# NL_Sheet1.net
KiCad netlist of a schematic drawn in Altium Designer
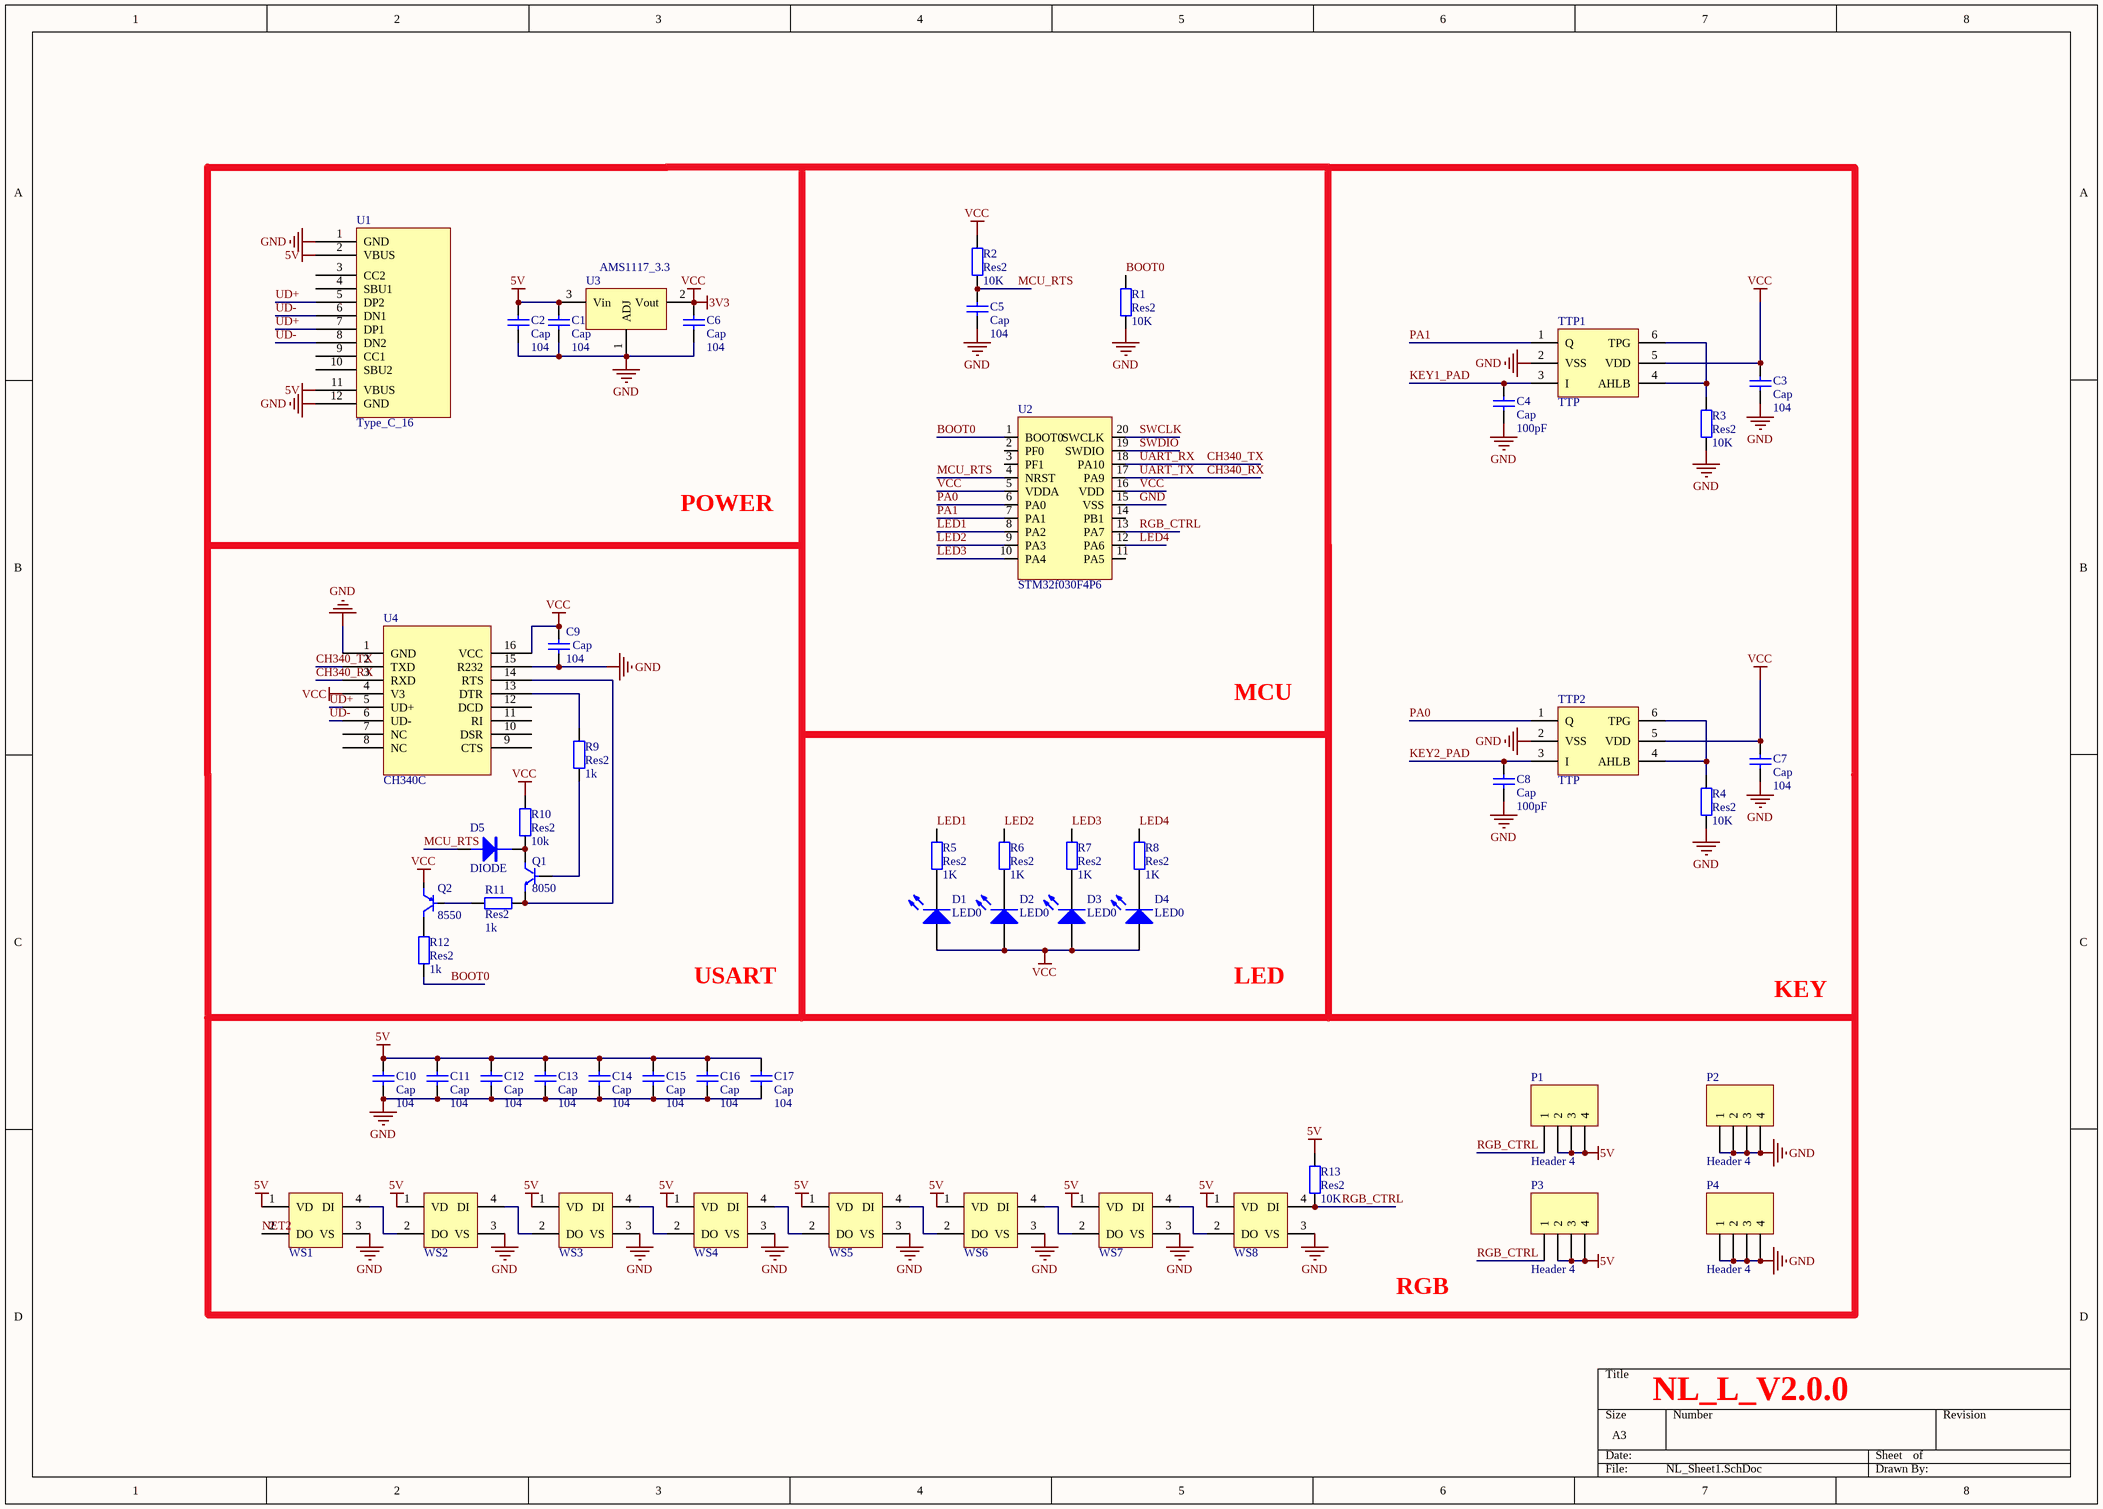
[diagram p0: NL_Sheet1.SchDoc]

(export (version "E")
  (design (tool "Eeschema 10.0.6"))
  (components
    (comp (ref "C1")
      (value "Cap")
      (footprint "0805")
      (description "Capacitor")
      (fields (field (name "ALTIUM_VALUE") "104") (field (name "PUBLISHER") "Altium Limited"))
      (libsource (lib "Miscellaneous Devices") (part "Cap"))
    )
    (comp (ref "C2")
      (value "Cap")
      (footprint "0805")
      (description "Capacitor")
      (fields (field (name "ALTIUM_VALUE") "104") (field (name "PUBLISHER") "Altium Limited"))
      (libsource (lib "Miscellaneous Devices") (part "Cap"))
    )
    (comp (ref "C3")
      (value "Cap")
      (footprint "0805")
      (description "Capacitor")
      (fields (field (name "ALTIUM_VALUE") "104") (field (name "PUBLISHER") "Altium Limited"))
      (libsource (lib "Miscellaneous Devices") (part "Cap"))
    )
    (comp (ref "C4")
      (value "Cap")
      (footprint "0805")
      (description "Capacitor")
      (fields (field (name "ALTIUM_VALUE") "100pF") (field (name "PUBLISHER") "Altium Limited"))
      (libsource (lib "Miscellaneous Devices") (part "Cap"))
    )
    (comp (ref "C5")
      (value "Cap")
      (footprint "0805")
      (description "Capacitor")
      (fields (field (name "ALTIUM_VALUE") "104") (field (name "PUBLISHER") "Altium Limited"))
      (libsource (lib "Miscellaneous Devices") (part "Cap"))
    )
    (comp (ref "C6")
      (value "Cap")
      (footprint "0805")
      (description "Capacitor")
      (fields (field (name "ALTIUM_VALUE") "104") (field (name "PUBLISHER") "Altium Limited"))
      (libsource (lib "Miscellaneous Devices") (part "Cap"))
    )
    (comp (ref "C7")
      (value "Cap")
      (footprint "0805")
      (description "Capacitor")
      (fields (field (name "ALTIUM_VALUE") "104") (field (name "PUBLISHER") "Altium Limited"))
      (libsource (lib "Miscellaneous Devices") (part "Cap"))
    )
    (comp (ref "C8")
      (value "Cap")
      (footprint "0805")
      (description "Capacitor")
      (fields (field (name "ALTIUM_VALUE") "100pF") (field (name "PUBLISHER") "Altium Limited"))
      (libsource (lib "Miscellaneous Devices") (part "Cap"))
    )
    (comp (ref "C9")
      (value "Cap")
      (footprint "0805")
      (description "Capacitor")
      (fields (field (name "ALTIUM_VALUE") "104") (field (name "PUBLISHER") "Altium Limited"))
      (libsource (lib "Miscellaneous Devices") (part "Cap"))
    )
    (comp (ref "C10")
      (value "Cap")
      (footprint "0805")
      (description "Capacitor")
      (fields (field (name "ALTIUM_VALUE") "104") (field (name "PUBLISHER") "Altium Limited"))
      (libsource (lib "NL_PCB_Project") (part "Cap"))
    )
    (comp (ref "C11")
      (value "Cap")
      (footprint "0805")
      (description "Capacitor")
      (fields (field (name "ALTIUM_VALUE") "104") (field (name "PUBLISHER") "Altium Limited"))
      (libsource (lib "NL_PCB_Project") (part "Cap"))
    )
    (comp (ref "C12")
      (value "Cap")
      (footprint "0805")
      (description "Capacitor")
      (fields (field (name "ALTIUM_VALUE") "104") (field (name "PUBLISHER") "Altium Limited"))
      (libsource (lib "NL_PCB_Project") (part "Cap"))
    )
    (comp (ref "C13")
      (value "Cap")
      (footprint "0805")
      (description "Capacitor")
      (fields (field (name "ALTIUM_VALUE") "104") (field (name "PUBLISHER") "Altium Limited"))
      (libsource (lib "NL_PCB_Project") (part "Cap"))
    )
    (comp (ref "C14")
      (value "Cap")
      (footprint "0805")
      (description "Capacitor")
      (fields (field (name "ALTIUM_VALUE") "104") (field (name "PUBLISHER") "Altium Limited"))
      (libsource (lib "NL_PCB_Project") (part "Cap"))
    )
    (comp (ref "C15")
      (value "Cap")
      (footprint "0805")
      (description "Capacitor")
      (fields (field (name "ALTIUM_VALUE") "104") (field (name "PUBLISHER") "Altium Limited"))
      (libsource (lib "NL_PCB_Project") (part "Cap"))
    )
    (comp (ref "C16")
      (value "Cap")
      (footprint "0805")
      (description "Capacitor")
      (fields (field (name "ALTIUM_VALUE") "104") (field (name "PUBLISHER") "Altium Limited"))
      (libsource (lib "NL_PCB_Project") (part "Cap"))
    )
    (comp (ref "C17")
      (value "Cap")
      (footprint "0805")
      (description "Capacitor")
      (fields (field (name "ALTIUM_VALUE") "104") (field (name "PUBLISHER") "Altium Limited"))
      (libsource (lib "NL_PCB_Project") (part "Cap"))
    )
    (comp (ref "D1")
      (value "LED0")
      (footprint "0805")
      (description "Typical INFRARED GaAs LED")
      (fields (field (name "PUBLISHER") "Altium Limited"))
      (libsource (lib "Miscellaneous Devices") (part "LED0"))
    )
    (comp (ref "D2")
      (value "LED0")
      (footprint "0805")
      (description "Typical INFRARED GaAs LED")
      (fields (field (name "PUBLISHER") "Altium Limited"))
      (libsource (lib "Miscellaneous Devices") (part "LED0"))
    )
    (comp (ref "D3")
      (value "LED0")
      (footprint "0805")
      (description "Typical INFRARED GaAs LED")
      (fields (field (name "PUBLISHER") "Altium Limited"))
      (libsource (lib "Miscellaneous Devices") (part "LED0"))
    )
    (comp (ref "D4")
      (value "LED0")
      (footprint "0805")
      (description "Typical INFRARED GaAs LED")
      (fields (field (name "PUBLISHER") "Altium Limited"))
      (libsource (lib "Miscellaneous Devices") (part "LED0"))
    )
    (comp (ref "D5") (value "DIODE") (footprint "0805L") (libsource (lib "常用1") (part "DIODE")))
    (comp (ref "P1")
      (value "Header 4")
      (footprint "HDR1X4")
      (description "Header, 4-Pin")
      (fields (field (name "PUBLISHER") "Altium Limited"))
      (libsource (lib "Miscellaneous Connectors") (part "Header 4"))
    )
    (comp (ref "P2")
      (value "Header 4")
      (footprint "HDR1X4")
      (description "Header, 4-Pin")
      (fields (field (name "PUBLISHER") "Altium Limited"))
      (libsource (lib "Miscellaneous Connectors") (part "Header 4"))
    )
    (comp (ref "P3")
      (value "Header 4")
      (footprint "HDR1X4")
      (description "Header, 4-Pin")
      (fields (field (name "PUBLISHER") "Altium Limited"))
      (libsource (lib "Miscellaneous Connectors") (part "Header 4"))
    )
    (comp (ref "P4")
      (value "Header 4")
      (footprint "HDR1X4")
      (description "Header, 4-Pin")
      (fields (field (name "PUBLISHER") "Altium Limited"))
      (libsource (lib "Miscellaneous Connectors") (part "Header 4"))
    )
    (comp (ref "Q1") (value "8050") (footprint "SOT23") (libsource (lib "NL_PCB_Project") (part "NPN")))
    (comp (ref "Q2") (value "8550") (footprint "SOT23") (libsource (lib "NL_PCB_Project") (part "PNP")))
    (comp (ref "R1")
      (value "Res2")
      (footprint "0805")
      (description "Resistor")
      (fields (field (name "ALTIUM_VALUE") "10K") (field (name "PUBLISHER") "Altium Limited"))
      (libsource (lib "Miscellaneous Devices") (part "Res2"))
    )
    (comp (ref "R2")
      (value "Res2")
      (footprint "0805")
      (description "Resistor")
      (fields (field (name "ALTIUM_VALUE") "10K") (field (name "PUBLISHER") "Altium Limited"))
      (libsource (lib "Miscellaneous Devices") (part "Res2"))
    )
    (comp (ref "R3")
      (value "Res2")
      (footprint "0805")
      (description "Resistor")
      (fields (field (name "ALTIUM_VALUE") "10K") (field (name "PUBLISHER") "Altium Limited"))
      (libsource (lib "Miscellaneous Devices") (part "Res2"))
    )
    (comp (ref "R4")
      (value "Res2")
      (footprint "0805")
      (description "Resistor")
      (fields (field (name "ALTIUM_VALUE") "10K") (field (name "PUBLISHER") "Altium Limited"))
      (libsource (lib "Miscellaneous Devices") (part "Res2"))
    )
    (comp (ref "R5")
      (value "Res2")
      (footprint "0805")
      (description "Resistor")
      (fields (field (name "ALTIUM_VALUE") "1K") (field (name "PUBLISHER") "Altium Limited"))
      (libsource (lib "Miscellaneous Devices") (part "Res2"))
    )
    (comp (ref "R6")
      (value "Res2")
      (footprint "0805")
      (description "Resistor")
      (fields (field (name "ALTIUM_VALUE") "1K") (field (name "PUBLISHER") "Altium Limited"))
      (libsource (lib "Miscellaneous Devices") (part "Res2"))
    )
    (comp (ref "R7")
      (value "Res2")
      (footprint "0805")
      (description "Resistor")
      (fields (field (name "ALTIUM_VALUE") "1K") (field (name "PUBLISHER") "Altium Limited"))
      (libsource (lib "Miscellaneous Devices") (part "Res2"))
    )
    (comp (ref "R8")
      (value "Res2")
      (footprint "0805")
      (description "Resistor")
      (fields (field (name "ALTIUM_VALUE") "1K") (field (name "PUBLISHER") "Altium Limited"))
      (libsource (lib "Miscellaneous Devices") (part "Res2"))
    )
    (comp (ref "R9")
      (value "Res2")
      (footprint "0805")
      (description "Resistor")
      (fields (field (name "ALTIUM_VALUE") "1k") (field (name "PUBLISHER") "Altium Limited"))
      (libsource (lib "") (part "Res2_1"))
    )
    (comp (ref "R10")
      (value "Res2")
      (footprint "0805")
      (description "Resistor")
      (fields (field (name "ALTIUM_VALUE") "10k") (field (name "PUBLISHER") "Altium Limited"))
      (libsource (lib "") (part "Res2_1"))
    )
    (comp (ref "R11")
      (value "Res2")
      (footprint "0805")
      (description "Resistor")
      (fields (field (name "ALTIUM_VALUE") "1k") (field (name "PUBLISHER") "Altium Limited"))
      (libsource (lib "") (part "Res2_2"))
    )
    (comp (ref "R12")
      (value "Res2")
      (footprint "0805")
      (description "Resistor")
      (fields (field (name "ALTIUM_VALUE") "1k") (field (name "PUBLISHER") "Altium Limited"))
      (libsource (lib "Miscellaneous Devices") (part "Res2"))
    )
    (comp (ref "R13")
      (value "Res2")
      (footprint "0805")
      (description "Resistor")
      (fields (field (name "ALTIUM_VALUE") "10K") (field (name "PUBLISHER") "Altium Limited"))
      (libsource (lib "Miscellaneous Devices") (part "Res2"))
    )
    (comp (ref "TTP1") (value "TTP") (footprint "SOT23-6L") (libsource (lib "常用1") (part "TTP223")))
    (comp (ref "TTP2") (value "TTP") (footprint "SOT23-6L") (libsource (lib "常用1") (part "TTP223")))
    (comp (ref "U1") (value "Type_C_16") (footprint "Type_C16") (libsource (lib "常用1") (part "Type_C_16")))
    (comp (ref "U2")
      (value "STM32f030F4P6")
      (footprint "SSOP20")
      (libsource (lib "ST Microcontrol") (part "STM32f030F4P6"))
    )
    (comp (ref "U3")
      (value "AMS1117_3.3")
      (footprint "SOT-223")
      (description "3-Terminal Adjustable Positive Voltage Regulator")
      (libsource (lib "稳压器件") (part "LM317"))
    )
    (comp (ref "U4") (value "CH340C") (footprint "SOP16") (libsource (lib "常用1") (part "CH340C")))
    (comp (ref "WS1") (value "WS2812") (footprint "WS2812") (libsource (lib "常用1") (part "WS2812")))
    (comp (ref "WS2") (value "WS2812") (footprint "WS2812") (libsource (lib "常用1") (part "WS2812")))
    (comp (ref "WS3") (value "WS2812") (footprint "WS2812") (libsource (lib "常用1") (part "WS2812")))
    (comp (ref "WS4") (value "WS2812") (footprint "WS2812") (libsource (lib "常用1") (part "WS2812")))
    (comp (ref "WS5") (value "WS2812") (footprint "WS2812") (libsource (lib "常用1") (part "WS2812")))
    (comp (ref "WS6") (value "WS2812") (footprint "WS2812") (libsource (lib "常用1") (part "WS2812")))
    (comp (ref "WS7") (value "WS2812") (footprint "WS2812") (libsource (lib "常用1") (part "WS2812")))
    (comp (ref "WS8") (value "WS2812") (footprint "WS2812") (libsource (lib "常用1") (part "WS2812")))
  )
  (nets
    (net (code "1") (name "/BOOT0") (class "Default")
      (node (ref "R1") (pin "2") (pinfunction "2_2") (pintype "passive"))
      (node (ref "R12") (pin "1") (pinfunction "1_1") (pintype "passive"))
      (node (ref "U2") (pin "1") (pinfunction "BOOT0_1") (pintype "passive"))
    )
    (net (code "2") (name "/CH340_RX") (class "Default")
      (node (ref "U2") (pin "17") (pinfunction "PA9_17") (pintype "passive"))
      (node (ref "U4") (pin "3") (pinfunction "RXD_3") (pintype "passive"))
    )
    (net (code "3") (name "/CH340_TX") (class "Default")
      (node (ref "U2") (pin "18") (pinfunction "PA10_18") (pintype "passive"))
      (node (ref "U4") (pin "2") (pinfunction "TXD_2") (pintype "passive"))
    )
    (net (code "4") (name "/KEY1_PAD") (class "Default")
      (node (ref "C4") (pin "2") (pinfunction "2_2") (pintype "passive"))
      (node (ref "TTP1") (pin "3") (pinfunction "I_3") (pintype "passive"))
    )
    (net (code "5") (name "/KEY2_PAD") (class "Default")
      (node (ref "C8") (pin "2") (pinfunction "2_2") (pintype "passive"))
      (node (ref "TTP2") (pin "3") (pinfunction "I_3") (pintype "passive"))
    )
    (net (code "6") (name "/LED1") (class "Default")
      (node (ref "R5") (pin "2") (pinfunction "2_2") (pintype "passive"))
      (node (ref "U2") (pin "8") (pinfunction "PA2_8") (pintype "passive"))
    )
    (net (code "7") (name "/LED2") (class "Default")
      (node (ref "R6") (pin "2") (pinfunction "2_2") (pintype "passive"))
      (node (ref "U2") (pin "9") (pinfunction "PA3_9") (pintype "passive"))
    )
    (net (code "8") (name "/LED3") (class "Default")
      (node (ref "R7") (pin "2") (pinfunction "2_2") (pintype "passive"))
      (node (ref "U2") (pin "10") (pinfunction "PA4_10") (pintype "passive"))
    )
    (net (code "9") (name "/LED4") (class "Default")
      (node (ref "R8") (pin "2") (pinfunction "2_2") (pintype "passive"))
      (node (ref "U2") (pin "12") (pinfunction "PA6_12") (pintype "passive"))
    )
    (net (code "10") (name "/MCU_RTS") (class "Default")
      (node (ref "C5") (pin "2") (pinfunction "2_2") (pintype "passive"))
      (node (ref "D5") (pin "1") (pintype "passive"))
      (node (ref "R2") (pin "1") (pinfunction "1_1") (pintype "passive"))
      (node (ref "U2") (pin "4") (pinfunction "NRST_4") (pintype "passive"))
    )
    (net (code "11") (name "/NET2") (class "Default")
      (node (ref "WS1") (pin "2") (pinfunction "DO_2") (pintype "passive"))
    )
    (net (code "12") (name "/PA0") (class "Default")
      (node (ref "TTP2") (pin "1") (pinfunction "Q_1") (pintype "passive"))
      (node (ref "U2") (pin "6") (pinfunction "PA0_6") (pintype "passive"))
    )
    (net (code "13") (name "/PA1") (class "Default")
      (node (ref "TTP1") (pin "1") (pinfunction "Q_1") (pintype "passive"))
      (node (ref "U2") (pin "7") (pinfunction "PA1_7") (pintype "passive"))
    )
    (net (code "14") (name "/RGB_CTRL") (class "Default")
      (node (ref "P1") (pin "1") (pinfunction "1_1") (pintype "passive"))
      (node (ref "P3") (pin "1") (pinfunction "1_1") (pintype "passive"))
      (node (ref "R13") (pin "1") (pinfunction "1_1") (pintype "passive"))
      (node (ref "U2") (pin "13") (pinfunction "PA7_13") (pintype "passive"))
      (node (ref "WS8") (pin "4") (pinfunction "DI_4") (pintype "passive"))
    )
    (net (code "15") (name "/SWCLK") (class "Default")
      (node (ref "U2") (pin "20") (pinfunction "SWCLK_20") (pintype "passive"))
    )
    (net (code "16") (name "/SWDIO") (class "Default")
      (node (ref "U2") (pin "19") (pinfunction "SWDIO_19") (pintype "passive"))
    )
    (net (code "17") (name "/UD+") (class "Default")
      (node (ref "U1") (pin "5") (pinfunction "DP2_5") (pintype "passive"))
      (node (ref "U1") (pin "7") (pinfunction "DP1_7") (pintype "passive"))
      (node (ref "U4") (pin "5") (pinfunction "UD+_5") (pintype "passive"))
    )
    (net (code "18") (name "/UD-") (class "Default")
      (node (ref "U1") (pin "6") (pinfunction "DN1_6") (pintype "passive"))
      (node (ref "U1") (pin "8") (pinfunction "DN2_8") (pintype "passive"))
      (node (ref "U4") (pin "6") (pinfunction "UD-_6") (pintype "passive"))
    )
    (net (code "19") (name "3V3") (class "Default")
      (node (ref "C3") (pin "2") (pinfunction "2_2") (pintype "passive"))
      (node (ref "C6") (pin "2") (pinfunction "2_2") (pintype "passive"))
      (node (ref "C7") (pin "2") (pinfunction "2_2") (pintype "passive"))
      (node (ref "C9") (pin "2") (pinfunction "2_2") (pintype "passive"))
      (node (ref "D1") (pin "1") (pinfunction "A_1") (pintype "passive"))
      (node (ref "D2") (pin "1") (pinfunction "A_1") (pintype "passive"))
      (node (ref "D3") (pin "1") (pinfunction "A_1") (pintype "passive"))
      (node (ref "D4") (pin "1") (pinfunction "A_1") (pintype "passive"))
      (node (ref "Q2") (pin "e") (pinfunction "e_e") (pintype "passive"))
      (node (ref "R10") (pin "1") (pinfunction "1_1") (pintype "passive"))
      (node (ref "R2") (pin "2") (pinfunction "2_2") (pintype "passive"))
      (node (ref "TTP1") (pin "5") (pinfunction "VDD_5") (pintype "passive"))
      (node (ref "TTP2") (pin "5") (pinfunction "VDD_5") (pintype "passive"))
      (node (ref "U2") (pin "16") (pinfunction "VDD_16") (pintype "passive"))
      (node (ref "U2") (pin "5") (pinfunction "VDDA_5") (pintype "passive"))
      (node (ref "U3") (pin "2") (pinfunction "Vout_2") (pintype "passive"))
      (node (ref "U4") (pin "16") (pinfunction "VCC_16") (pintype "passive"))
      (node (ref "U4") (pin "4") (pinfunction "V3_4") (pintype "passive"))
    )
    (net (code "20") (name "5V") (class "Default")
      (node (ref "C1") (pin "2") (pinfunction "2_2") (pintype "passive"))
      (node (ref "C10") (pin "2") (pinfunction "2_2") (pintype "passive"))
      (node (ref "C11") (pin "2") (pinfunction "2_2") (pintype "passive"))
      (node (ref "C12") (pin "2") (pinfunction "2_2") (pintype "passive"))
      (node (ref "C13") (pin "2") (pinfunction "2_2") (pintype "passive"))
      (node (ref "C14") (pin "2") (pinfunction "2_2") (pintype "passive"))
      (node (ref "C15") (pin "2") (pinfunction "2_2") (pintype "passive"))
      (node (ref "C16") (pin "2") (pinfunction "2_2") (pintype "passive"))
      (node (ref "C17") (pin "2") (pinfunction "2_2") (pintype "passive"))
      (node (ref "C2") (pin "2") (pinfunction "2_2") (pintype "passive"))
      (node (ref "P1") (pin "2") (pinfunction "2_2") (pintype "passive"))
      (node (ref "P1") (pin "3") (pinfunction "3_3") (pintype "passive"))
      (node (ref "P1") (pin "4") (pinfunction "4_4") (pintype "passive"))
      (node (ref "P3") (pin "2") (pinfunction "2_2") (pintype "passive"))
      (node (ref "P3") (pin "3") (pinfunction "3_3") (pintype "passive"))
      (node (ref "P3") (pin "4") (pinfunction "4_4") (pintype "passive"))
      (node (ref "R13") (pin "2") (pinfunction "2_2") (pintype "passive"))
      (node (ref "U1") (pin "11") (pinfunction "VBUS_11") (pintype "passive"))
      (node (ref "U1") (pin "2") (pinfunction "VBUS_2") (pintype "passive"))
      (node (ref "U3") (pin "3") (pinfunction "Vin_3") (pintype "passive"))
      (node (ref "WS1") (pin "1") (pinfunction "VD_1") (pintype "passive"))
      (node (ref "WS2") (pin "1") (pinfunction "VD_1") (pintype "passive"))
      (node (ref "WS3") (pin "1") (pinfunction "VD_1") (pintype "passive"))
      (node (ref "WS4") (pin "1") (pinfunction "VD_1") (pintype "passive"))
      (node (ref "WS5") (pin "1") (pinfunction "VD_1") (pintype "passive"))
      (node (ref "WS6") (pin "1") (pinfunction "VD_1") (pintype "passive"))
      (node (ref "WS7") (pin "1") (pinfunction "VD_1") (pintype "passive"))
      (node (ref "WS8") (pin "1") (pinfunction "VD_1") (pintype "passive"))
    )
    (net (code "21") (name "GND") (class "Default")
      (node (ref "C1") (pin "1") (pinfunction "1_1") (pintype "passive"))
      (node (ref "C10") (pin "1") (pinfunction "1_1") (pintype "passive"))
      (node (ref "C11") (pin "1") (pinfunction "1_1") (pintype "passive"))
      (node (ref "C12") (pin "1") (pinfunction "1_1") (pintype "passive"))
      (node (ref "C13") (pin "1") (pinfunction "1_1") (pintype "passive"))
      (node (ref "C14") (pin "1") (pinfunction "1_1") (pintype "passive"))
      (node (ref "C15") (pin "1") (pinfunction "1_1") (pintype "passive"))
      (node (ref "C16") (pin "1") (pinfunction "1_1") (pintype "passive"))
      (node (ref "C17") (pin "1") (pinfunction "1_1") (pintype "passive"))
      (node (ref "C2") (pin "1") (pinfunction "1_1") (pintype "passive"))
      (node (ref "C3") (pin "1") (pinfunction "1_1") (pintype "passive"))
      (node (ref "C4") (pin "1") (pinfunction "1_1") (pintype "passive"))
      (node (ref "C5") (pin "1") (pinfunction "1_1") (pintype "passive"))
      (node (ref "C6") (pin "1") (pinfunction "1_1") (pintype "passive"))
      (node (ref "C7") (pin "1") (pinfunction "1_1") (pintype "passive"))
      (node (ref "C8") (pin "1") (pinfunction "1_1") (pintype "passive"))
      (node (ref "C9") (pin "1") (pinfunction "1_1") (pintype "passive"))
      (node (ref "P2") (pin "1") (pinfunction "1_1") (pintype "passive"))
      (node (ref "P2") (pin "2") (pinfunction "2_2") (pintype "passive"))
      (node (ref "P2") (pin "3") (pinfunction "3_3") (pintype "passive"))
      (node (ref "P2") (pin "4") (pinfunction "4_4") (pintype "passive"))
      (node (ref "P4") (pin "1") (pinfunction "1_1") (pintype "passive"))
      (node (ref "P4") (pin "2") (pinfunction "2_2") (pintype "passive"))
      (node (ref "P4") (pin "3") (pinfunction "3_3") (pintype "passive"))
      (node (ref "P4") (pin "4") (pinfunction "4_4") (pintype "passive"))
      (node (ref "R1") (pin "1") (pinfunction "1_1") (pintype "passive"))
      (node (ref "R3") (pin "1") (pinfunction "1_1") (pintype "passive"))
      (node (ref "R4") (pin "1") (pinfunction "1_1") (pintype "passive"))
      (node (ref "TTP1") (pin "2") (pinfunction "VSS_2") (pintype "passive"))
      (node (ref "TTP2") (pin "2") (pinfunction "VSS_2") (pintype "passive"))
      (node (ref "U1") (pin "1") (pinfunction "GND_1") (pintype "passive"))
      (node (ref "U1") (pin "12") (pinfunction "GND_12") (pintype "passive"))
      (node (ref "U2") (pin "15") (pinfunction "VSS_15") (pintype "passive"))
      (node (ref "U3") (pin "1") (pinfunction "ADJ_1") (pintype "passive"))
      (node (ref "U4") (pin "1") (pinfunction "GND_1") (pintype "passive"))
      (node (ref "U4") (pin "15") (pinfunction "R232_15") (pintype "passive"))
      (node (ref "WS1") (pin "3") (pinfunction "VS_3") (pintype "passive"))
      (node (ref "WS2") (pin "3") (pinfunction "VS_3") (pintype "passive"))
      (node (ref "WS3") (pin "3") (pinfunction "VS_3") (pintype "passive"))
      (node (ref "WS4") (pin "3") (pinfunction "VS_3") (pintype "passive"))
      (node (ref "WS5") (pin "3") (pinfunction "VS_3") (pintype "passive"))
      (node (ref "WS6") (pin "3") (pinfunction "VS_3") (pintype "passive"))
      (node (ref "WS7") (pin "3") (pinfunction "VS_3") (pintype "passive"))
      (node (ref "WS8") (pin "3") (pinfunction "VS_3") (pintype "passive"))
    )
    (net (code "22") (name "Net-(D1-K)") (class "Default")
      (node (ref "D1") (pin "2") (pinfunction "K_2") (pintype "passive"))
      (node (ref "R5") (pin "1") (pinfunction "1_1") (pintype "passive"))
    )
    (net (code "23") (name "Net-(D2-K)") (class "Default")
      (node (ref "D2") (pin "2") (pinfunction "K_2") (pintype "passive"))
      (node (ref "R6") (pin "1") (pinfunction "1_1") (pintype "passive"))
    )
    (net (code "24") (name "Net-(D3-K)") (class "Default")
      (node (ref "D3") (pin "2") (pinfunction "K_2") (pintype "passive"))
      (node (ref "R7") (pin "1") (pinfunction "1_1") (pintype "passive"))
    )
    (net (code "25") (name "Net-(D4-K)") (class "Default")
      (node (ref "D4") (pin "2") (pinfunction "K_2") (pintype "passive"))
      (node (ref "R8") (pin "1") (pinfunction "1_1") (pintype "passive"))
    )
    (net (code "26") (name "Net-(D5-Pad2)") (class "Default")
      (node (ref "D5") (pin "2") (pintype "passive"))
      (node (ref "Q1") (pin "c") (pinfunction "c_c") (pintype "passive"))
      (node (ref "R10") (pin "2") (pinfunction "2_2") (pintype "passive"))
    )
    (net (code "27") (name "Net-(Q1-Padb)") (class "Default")
      (node (ref "Q1") (pin "b") (pinfunction "b_b") (pintype "passive"))
      (node (ref "R9") (pin "2") (pinfunction "2_2") (pintype "passive"))
    )
    (net (code "28") (name "Net-(Q2-Padb)") (class "Default")
      (node (ref "Q2") (pin "b") (pinfunction "b_b") (pintype "passive"))
      (node (ref "R11") (pin "1") (pinfunction "1_1") (pintype "passive"))
    )
    (net (code "29") (name "Net-(Q2-Padc)") (class "Default")
      (node (ref "Q2") (pin "c") (pinfunction "c_c") (pintype "passive"))
      (node (ref "R12") (pin "2") (pinfunction "2_2") (pintype "passive"))
    )
    (net (code "30") (name "Net-(TTP1-AHLB)") (class "Default")
      (node (ref "R3") (pin "2") (pinfunction "2_2") (pintype "passive"))
      (node (ref "TTP1") (pin "4") (pinfunction "AHLB_4") (pintype "passive"))
      (node (ref "TTP1") (pin "6") (pinfunction "TPG_6") (pintype "passive"))
    )
    (net (code "31") (name "Net-(TTP2-AHLB)") (class "Default")
      (node (ref "R4") (pin "2") (pinfunction "2_2") (pintype "passive"))
      (node (ref "TTP2") (pin "4") (pinfunction "AHLB_4") (pintype "passive"))
      (node (ref "TTP2") (pin "6") (pinfunction "TPG_6") (pintype "passive"))
    )
    (net (code "32") (name "Net-(U4-DTR)") (class "Default")
      (node (ref "R9") (pin "1") (pinfunction "1_1") (pintype "passive"))
      (node (ref "U4") (pin "13") (pinfunction "DTR_13") (pintype "passive"))
    )
    (net (code "33") (name "Net-(U4-RTS)") (class "Default")
      (node (ref "Q1") (pin "e") (pinfunction "e_e") (pintype "passive"))
      (node (ref "R11") (pin "2") (pinfunction "2_2") (pintype "passive"))
      (node (ref "U4") (pin "14") (pinfunction "RTS_14") (pintype "passive"))
    )
    (net (code "34") (name "Net-(WS1-DI)") (class "Default")
      (node (ref "WS1") (pin "4") (pinfunction "DI_4") (pintype "passive"))
      (node (ref "WS2") (pin "2") (pinfunction "DO_2") (pintype "passive"))
    )
    (net (code "35") (name "Net-(WS2-DI)") (class "Default")
      (node (ref "WS2") (pin "4") (pinfunction "DI_4") (pintype "passive"))
      (node (ref "WS3") (pin "2") (pinfunction "DO_2") (pintype "passive"))
    )
    (net (code "36") (name "Net-(WS3-DI)") (class "Default")
      (node (ref "WS3") (pin "4") (pinfunction "DI_4") (pintype "passive"))
      (node (ref "WS4") (pin "2") (pinfunction "DO_2") (pintype "passive"))
    )
    (net (code "37") (name "Net-(WS4-DI)") (class "Default")
      (node (ref "WS4") (pin "4") (pinfunction "DI_4") (pintype "passive"))
      (node (ref "WS5") (pin "2") (pinfunction "DO_2") (pintype "passive"))
    )
    (net (code "38") (name "Net-(WS5-DI)") (class "Default")
      (node (ref "WS5") (pin "4") (pinfunction "DI_4") (pintype "passive"))
      (node (ref "WS6") (pin "2") (pinfunction "DO_2") (pintype "passive"))
    )
    (net (code "39") (name "Net-(WS6-DI)") (class "Default")
      (node (ref "WS6") (pin "4") (pinfunction "DI_4") (pintype "passive"))
      (node (ref "WS7") (pin "2") (pinfunction "DO_2") (pintype "passive"))
    )
    (net (code "40") (name "Net-(WS7-DI)") (class "Default")
      (node (ref "WS7") (pin "4") (pinfunction "DI_4") (pintype "passive"))
      (node (ref "WS8") (pin "2") (pinfunction "DO_2") (pintype "passive"))
    )
    (net (code "41") (name "unconnected-(U1-CC1-Pad9)") (class "Default")
      (node (ref "U1") (pin "9") (pinfunction "CC1_9") (pintype "passive"))
    )
    (net (code "42") (name "unconnected-(U1-CC2-Pad3)") (class "Default")
      (node (ref "U1") (pin "3") (pinfunction "CC2_3") (pintype "passive"))
    )
    (net (code "43") (name "unconnected-(U1-SBU1-Pad4)") (class "Default")
      (node (ref "U1") (pin "4") (pinfunction "SBU1_4") (pintype "passive"))
    )
    (net (code "44") (name "unconnected-(U1-SBU2-Pad10)") (class "Default")
      (node (ref "U1") (pin "10") (pinfunction "SBU2_10") (pintype "passive"))
    )
    (net (code "45") (name "unconnected-(U2-PA5-Pad11)") (class "Default")
      (node (ref "U2") (pin "11") (pinfunction "PA5_11") (pintype "passive"))
    )
    (net (code "46") (name "unconnected-(U2-PB1-Pad14)") (class "Default")
      (node (ref "U2") (pin "14") (pinfunction "PB1_14") (pintype "passive"))
    )
    (net (code "47") (name "unconnected-(U2-PF0-Pad2)") (class "Default")
      (node (ref "U2") (pin "2") (pinfunction "PF0_2") (pintype "passive"))
    )
    (net (code "48") (name "unconnected-(U2-PF1-Pad3)") (class "Default")
      (node (ref "U2") (pin "3") (pinfunction "PF1_3") (pintype "passive"))
    )
    (net (code "49") (name "unconnected-(U4-CTS-Pad9)") (class "Default")
      (node (ref "U4") (pin "9") (pinfunction "CTS_9") (pintype "passive"))
    )
    (net (code "50") (name "unconnected-(U4-DCD-Pad12)") (class "Default")
      (node (ref "U4") (pin "12") (pinfunction "DCD_12") (pintype "passive"))
    )
    (net (code "51") (name "unconnected-(U4-DSR-Pad10)") (class "Default")
      (node (ref "U4") (pin "10") (pinfunction "DSR_10") (pintype "passive"))
    )
    (net (code "52") (name "unconnected-(U4-NC-Pad7)") (class "Default")
      (node (ref "U4") (pin "7") (pinfunction "NC_7") (pintype "passive"))
    )
    (net (code "53") (name "unconnected-(U4-NC-Pad8)") (class "Default")
      (node (ref "U4") (pin "8") (pinfunction "NC_8") (pintype "passive"))
    )
    (net (code "54") (name "unconnected-(U4-RI-Pad11)") (class "Default")
      (node (ref "U4") (pin "11") (pinfunction "RI_11") (pintype "passive"))
    )
  )
)
